# pclone2_panel.net
KiCad netlist of a schematic drawn in EAGLE
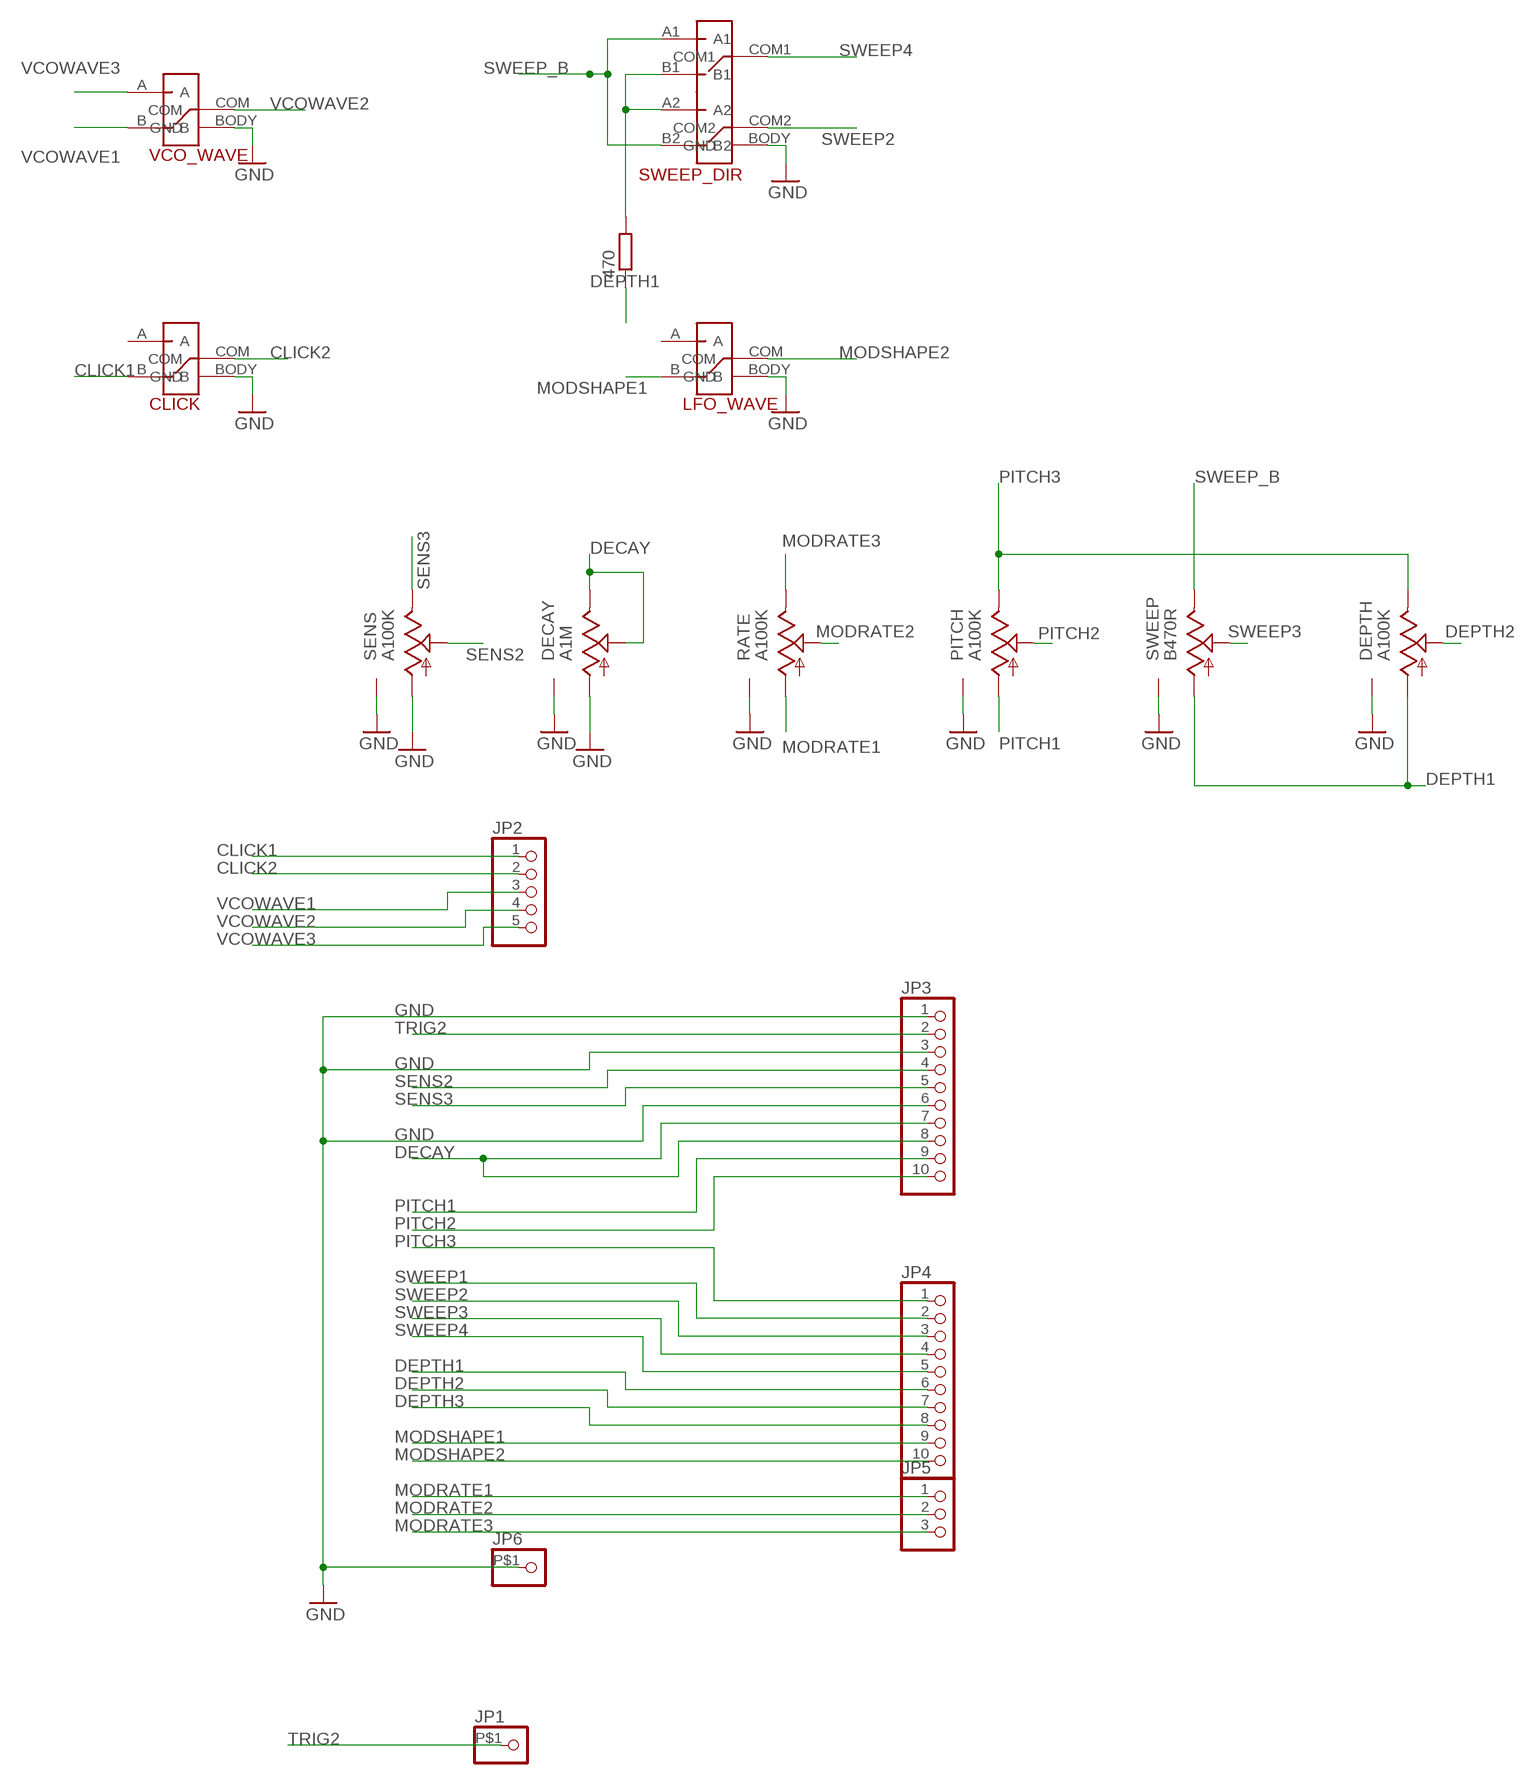
[diagram p0: schematic, sheet 1]

(export (version "E")
  (design (tool "Eeschema 10.0.6"))
  (components
    (comp (ref "470")
      (value "R-EU_R0805")
      (footprint "eagle-import:R0805")
      (libsource (lib "eagle-import") (part "R-EU_R0805"))
    )
    (comp (ref "CLICK")
      (value "SPD_SMTD")
      (footprint "eagle-import:SPDT_SMTD")
      (libsource (lib "eagle-import") (part "SPD_SMTD"))
    )
    (comp (ref "DECAY")
      (value "A1M")
      (footprint "eagle-import:16MM_POT_SMTD")
      (libsource (lib "eagle-import") (part "16MM_POT_SMTD"))
    )
    (comp (ref "DEPTH")
      (value "A100K")
      (footprint "eagle-import:16MM_POT_SMTD")
      (libsource (lib "eagle-import") (part "16MM_POT_SMTD"))
    )
    (comp (ref "JP1")
      (value "PINHD-1X1SMT")
      (footprint "eagle-import:PINHEADPAD")
      (libsource (lib "eagle-import") (part "PINHD-1X1SMT"))
    )
    (comp (ref "JP2")
      (value "HEADER-1X5SMT")
      (footprint "eagle-import:1X05_SMT")
      (libsource (lib "eagle-import") (part "HEADER-1X5SMT"))
    )
    (comp (ref "JP3")
      (value "HEADER-1X10SMT")
      (footprint "eagle-import:1X10_SMT")
      (libsource (lib "eagle-import") (part "HEADER-1X10SMT"))
    )
    (comp (ref "JP4")
      (value "HEADER-1X10SMT")
      (footprint "eagle-import:1X10_SMT")
      (libsource (lib "eagle-import") (part "HEADER-1X10SMT"))
    )
    (comp (ref "JP5")
      (value "HEADER-1X3SMT")
      (footprint "eagle-import:1X03_SMT")
      (libsource (lib "eagle-import") (part "HEADER-1X3SMT"))
    )
    (comp (ref "JP6")
      (value "PINHD-1X1SMT")
      (footprint "eagle-import:PINHEADPAD")
      (libsource (lib "eagle-import") (part "PINHD-1X1SMT"))
    )
    (comp (ref "LFO_WAVE")
      (value "SPD_SMTD")
      (footprint "eagle-import:SPDT_SMTD")
      (libsource (lib "eagle-import") (part "SPD_SMTD"))
    )
    (comp (ref "PITCH")
      (value "A100K")
      (footprint "eagle-import:16MM_POT_SMTD")
      (libsource (lib "eagle-import") (part "16MM_POT_SMTD"))
    )
    (comp (ref "RATE")
      (value "A100K")
      (footprint "eagle-import:16MM_POT_SMTD")
      (libsource (lib "eagle-import") (part "16MM_POT_SMTD"))
    )
    (comp (ref "SENS")
      (value "A100K")
      (footprint "eagle-import:16MM_POT_SMTD")
      (libsource (lib "eagle-import") (part "16MM_POT_SMTD"))
    )
    (comp (ref "SWEEP")
      (value "B470R")
      (footprint "eagle-import:16MM_POT_SMTD")
      (libsource (lib "eagle-import") (part "16MM_POT_SMTD"))
    )
    (comp (ref "SWEEP_DIR")
      (value "DPDT_SMTD")
      (footprint "eagle-import:DPDT_SMTD")
      (libsource (lib "eagle-import") (part "DPDT_SMTD"))
    )
    (comp (ref "VCO_WAVE")
      (value "SPD_SMTD")
      (footprint "eagle-import:SPDT_SMTD")
      (libsource (lib "eagle-import") (part "SPD_SMTD"))
    )
  )
  (nets
    (net (code "1") (name "/CLICK1") (class "Default")
      (node (ref "CLICK") (pin "B") (pinfunction "B_B") (pintype "bidirectional"))
      (node (ref "JP2") (pin "1") (pinfunction "1_1") (pintype "passive"))
    )
    (net (code "2") (name "/CLICK2") (class "Default")
      (node (ref "CLICK") (pin "COM") (pinfunction "COM_COM") (pintype "bidirectional"))
      (node (ref "JP2") (pin "2") (pinfunction "2_2") (pintype "passive"))
    )
    (net (code "3") (name "/DECAY") (class "Default")
      (node (ref "DECAY") (pin "B") (pinfunction "B_B") (pintype "passive"))
      (node (ref "DECAY") (pin "W") (pinfunction "W_W") (pintype "passive"))
      (node (ref "JP3") (pin "7") (pinfunction "7_7") (pintype "passive"))
      (node (ref "JP3") (pin "8") (pinfunction "8_8") (pintype "passive"))
    )
    (net (code "4") (name "/DEPTH1") (class "Default")
      (node (ref "470") (pin "1") (pinfunction "1_1") (pintype "passive"))
      (node (ref "DEPTH") (pin "A") (pinfunction "A_A") (pintype "passive"))
      (node (ref "JP4") (pin "6") (pinfunction "6_6") (pintype "passive"))
      (node (ref "SWEEP") (pin "A") (pinfunction "A_A") (pintype "passive"))
    )
    (net (code "5") (name "/DEPTH2") (class "Default")
      (node (ref "DEPTH") (pin "W") (pinfunction "W_W") (pintype "passive"))
      (node (ref "JP4") (pin "7") (pinfunction "7_7") (pintype "passive"))
    )
    (net (code "6") (name "/DEPTH3") (class "Default")
      (node (ref "JP4") (pin "8") (pinfunction "8_8") (pintype "passive"))
    )
    (net (code "7") (name "/MODRATE1") (class "Default")
      (node (ref "JP5") (pin "1") (pinfunction "1_1") (pintype "passive"))
      (node (ref "RATE") (pin "A") (pinfunction "A_A") (pintype "passive"))
    )
    (net (code "8") (name "/MODRATE2") (class "Default")
      (node (ref "JP5") (pin "2") (pinfunction "2_2") (pintype "passive"))
      (node (ref "RATE") (pin "W") (pinfunction "W_W") (pintype "passive"))
    )
    (net (code "9") (name "/MODRATE3") (class "Default")
      (node (ref "JP5") (pin "3") (pinfunction "3_3") (pintype "passive"))
      (node (ref "RATE") (pin "B") (pinfunction "B_B") (pintype "passive"))
    )
    (net (code "10") (name "/MODSHAPE1") (class "Default")
      (node (ref "JP4") (pin "9") (pinfunction "9_9") (pintype "passive"))
      (node (ref "LFO_WAVE") (pin "B") (pinfunction "B_B") (pintype "bidirectional"))
    )
    (net (code "11") (name "/MODSHAPE2") (class "Default")
      (node (ref "JP4") (pin "10") (pinfunction "10_10") (pintype "passive"))
      (node (ref "LFO_WAVE") (pin "COM") (pinfunction "COM_COM") (pintype "bidirectional"))
    )
    (net (code "12") (name "/PITCH1") (class "Default")
      (node (ref "JP3") (pin "9") (pinfunction "9_9") (pintype "passive"))
      (node (ref "PITCH") (pin "A") (pinfunction "A_A") (pintype "passive"))
    )
    (net (code "13") (name "/PITCH2") (class "Default")
      (node (ref "JP3") (pin "10") (pinfunction "10_10") (pintype "passive"))
      (node (ref "PITCH") (pin "W") (pinfunction "W_W") (pintype "passive"))
    )
    (net (code "14") (name "/PITCH3") (class "Default")
      (node (ref "DEPTH") (pin "B") (pinfunction "B_B") (pintype "passive"))
      (node (ref "JP4") (pin "1") (pinfunction "1_1") (pintype "passive"))
      (node (ref "PITCH") (pin "B") (pinfunction "B_B") (pintype "passive"))
    )
    (net (code "15") (name "/SENS2") (class "Default")
      (node (ref "JP3") (pin "4") (pinfunction "4_4") (pintype "passive"))
      (node (ref "SENS") (pin "W") (pinfunction "W_W") (pintype "passive"))
    )
    (net (code "16") (name "/SENS3") (class "Default")
      (node (ref "JP3") (pin "5") (pinfunction "5_5") (pintype "passive"))
      (node (ref "SENS") (pin "B") (pinfunction "B_B") (pintype "passive"))
    )
    (net (code "17") (name "/SWEEP1") (class "Default")
      (node (ref "JP4") (pin "2") (pinfunction "2_2") (pintype "passive"))
    )
    (net (code "18") (name "/SWEEP2") (class "Default")
      (node (ref "JP4") (pin "3") (pinfunction "3_3") (pintype "passive"))
      (node (ref "SWEEP_DIR") (pin "COM2") (pinfunction "COM2_COM2") (pintype "bidirectional"))
    )
    (net (code "19") (name "/SWEEP3") (class "Default")
      (node (ref "JP4") (pin "4") (pinfunction "4_4") (pintype "passive"))
      (node (ref "SWEEP") (pin "W") (pinfunction "W_W") (pintype "passive"))
    )
    (net (code "20") (name "/SWEEP4") (class "Default")
      (node (ref "JP4") (pin "5") (pinfunction "5_5") (pintype "passive"))
      (node (ref "SWEEP_DIR") (pin "COM1") (pinfunction "COM1_COM1") (pintype "bidirectional"))
    )
    (net (code "21") (name "/SWEEP_B") (class "Default")
      (node (ref "SWEEP") (pin "B") (pinfunction "B_B") (pintype "passive"))
      (node (ref "SWEEP_DIR") (pin "A1") (pinfunction "A1_A1") (pintype "bidirectional"))
      (node (ref "SWEEP_DIR") (pin "B2") (pinfunction "B2_B2") (pintype "bidirectional"))
    )
    (net (code "22") (name "/TRIG2") (class "Default")
      (node (ref "JP1") (pin "P$1") (pinfunction "1_P$1") (pintype "passive"))
      (node (ref "JP3") (pin "2") (pinfunction "2_2") (pintype "passive"))
    )
    (net (code "23") (name "/VCOWAVE1") (class "Default")
      (node (ref "JP2") (pin "3") (pinfunction "3_3") (pintype "passive"))
      (node (ref "VCO_WAVE") (pin "B") (pinfunction "B_B") (pintype "bidirectional"))
    )
    (net (code "24") (name "/VCOWAVE2") (class "Default")
      (node (ref "JP2") (pin "4") (pinfunction "4_4") (pintype "passive"))
      (node (ref "VCO_WAVE") (pin "COM") (pinfunction "COM_COM") (pintype "bidirectional"))
    )
    (net (code "25") (name "/VCOWAVE3") (class "Default")
      (node (ref "JP2") (pin "5") (pinfunction "5_5") (pintype "passive"))
      (node (ref "VCO_WAVE") (pin "A") (pinfunction "A_A") (pintype "bidirectional"))
    )
    (net (code "26") (name "GND") (class "Default")
      (node (ref "CLICK") (pin "BODY") (pinfunction "GND_BODY") (pintype "bidirectional"))
      (node (ref "DECAY") (pin "A") (pinfunction "A_A") (pintype "passive"))
      (node (ref "DECAY") (pin "BODY") (pinfunction "GND_BODY") (pintype "power_in"))
      (node (ref "DEPTH") (pin "BODY") (pinfunction "GND_BODY") (pintype "power_in"))
      (node (ref "JP3") (pin "1") (pinfunction "1_1") (pintype "passive"))
      (node (ref "JP3") (pin "3") (pinfunction "3_3") (pintype "passive"))
      (node (ref "JP3") (pin "6") (pinfunction "6_6") (pintype "passive"))
      (node (ref "JP6") (pin "P$1") (pinfunction "1_P$1") (pintype "passive"))
      (node (ref "LFO_WAVE") (pin "BODY") (pinfunction "GND_BODY") (pintype "bidirectional"))
      (node (ref "PITCH") (pin "BODY") (pinfunction "GND_BODY") (pintype "power_in"))
      (node (ref "RATE") (pin "BODY") (pinfunction "GND_BODY") (pintype "power_in"))
      (node (ref "SENS") (pin "A") (pinfunction "A_A") (pintype "passive"))
      (node (ref "SENS") (pin "BODY") (pinfunction "GND_BODY") (pintype "power_in"))
      (node (ref "SWEEP") (pin "BODY") (pinfunction "GND_BODY") (pintype "power_in"))
      (node (ref "SWEEP_DIR") (pin "BODY") (pinfunction "GND_BODY") (pintype "bidirectional"))
      (node (ref "VCO_WAVE") (pin "BODY") (pinfunction "GND_BODY") (pintype "bidirectional"))
    )
    (net (code "27") (name "Net-(470-Pad2)") (class "Default")
      (node (ref "470") (pin "2") (pinfunction "2_2") (pintype "passive"))
      (node (ref "SWEEP_DIR") (pin "A2") (pinfunction "A2_A2") (pintype "bidirectional"))
      (node (ref "SWEEP_DIR") (pin "B1") (pinfunction "B1_B1") (pintype "bidirectional"))
    )
    (net (code "28") (name "unconnected-(CLICK-PadA)") (class "Default")
      (node (ref "CLICK") (pin "A") (pinfunction "A_A") (pintype "bidirectional"))
    )
    (net (code "29") (name "unconnected-(LFO_WAVE-PadA)") (class "Default")
      (node (ref "LFO_WAVE") (pin "A") (pinfunction "A_A") (pintype "bidirectional"))
    )
  )
)
